# SDCARD.net
KiCad netlist of a schematic drawn in Altium Designer
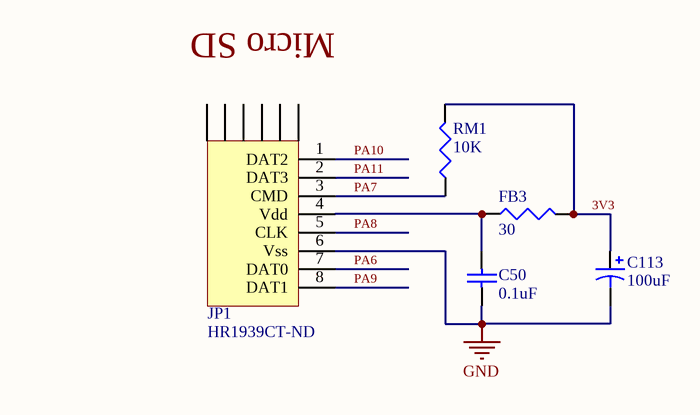
[diagram p0: SDCARD.SchDoc]

(export (version "E")
  (design (tool "Eeschema 10.0.6"))
  (components
    (comp (ref "C50")
      (value "0.1uF")
      (footprint "CAPC2008X06N")
      (description "CAP CER 0.1UF 50V 10% X7R 0805")
      (fields (field (name "Comment") "Kemet_0805_a_0.1uF"))
      (libsource (lib "Capacitors") (part "Kemet_0805_a_0.1uF"))
    )
    (comp (ref "C113")
      (value "100uF")
      (footprint "6032")
      (description "CAP TANT 100UF 10V 10% LOESR SMD")
      (fields (field (name "Comment") "TantCap_6032_100uF"))
      (libsource (lib "my_KEMET") (part "TantCap_6032_100uF"))
    )
    (comp (ref "FB3")
      (value "Murata_a_0805_30_Ohm_100Mhz")
      (footprint "0805")
      (description "FERRITE CHIP 30 OHM 3000MA 0805")
      (fields (field (name "VALUE @ 100MHZ") "30"))
      (libsource (lib "Filters") (part "Murata_a_0805_30_Ohm_100Mhz"))
    )
    (comp (ref "JP1")
      (value "MicroSD Connector")
      (footprint "DM3AT-SF-PEJ")
      (description "CONN MICRO SD R/A PUSH-PUSH SMD")
      (fields (field (name "SUPPLIER PART NUMBER 1") "HR1939CT-ND"))
      (libsource (lib "Hirose Electric CO LTD") (part "MicroSD Connector"))
    )
    (comp (ref "RM1")
      (value "10K")
      (footprint "RES0805")
      (description "RES 10.0K OHM 1/10W .5% 0805 SMD")
      (fields (field (name "Comment") "Susumu_0805_b2_10K"))
      (libsource (lib "Resistors") (part "Susumu_0805_b2_10K"))
    )
  )
  (nets
    (net (code "1") (name "/3V3") (class "Default")
      (node (ref "C113") (pin "1") (pinfunction "1_1") (pintype "passive"))
      (node (ref "FB3") (pin "2") (pinfunction "2_2") (pintype "passive"))
      (node (ref "RM1") (pin "2") (pinfunction "2_2") (pintype "passive"))
    )
    (net (code "2") (name "/PA6") (class "Default")
      (node (ref "JP1") (pin "7") (pinfunction "DAT0_7") (pintype "passive"))
    )
    (net (code "3") (name "/PA7") (class "Default")
      (node (ref "JP1") (pin "3") (pinfunction "CMD_3") (pintype "passive"))
      (node (ref "RM1") (pin "1") (pinfunction "1_1") (pintype "passive"))
    )
    (net (code "4") (name "/PA8") (class "Default")
      (node (ref "JP1") (pin "5") (pinfunction "CLK_5") (pintype "passive"))
    )
    (net (code "5") (name "/PA9") (class "Default")
      (node (ref "JP1") (pin "8") (pinfunction "DAT1_8") (pintype "passive"))
    )
    (net (code "6") (name "/PA10") (class "Default")
      (node (ref "JP1") (pin "1") (pinfunction "DAT2_1") (pintype "passive"))
    )
    (net (code "7") (name "/PA11") (class "Default")
      (node (ref "JP1") (pin "2") (pinfunction "DAT3_2") (pintype "passive"))
    )
    (net (code "8") (name "GND") (class "Default")
      (node (ref "C113") (pin "2") (pinfunction "2_2") (pintype "passive"))
      (node (ref "C50") (pin "1") (pinfunction "1_1") (pintype "passive"))
      (node (ref "JP1") (pin "6") (pinfunction "Vss_6") (pintype "passive"))
    )
    (net (code "9") (name "Net-(JP1-Vdd)") (class "Default")
      (node (ref "C50") (pin "2") (pinfunction "2_2") (pintype "passive"))
      (node (ref "FB3") (pin "1") (pinfunction "1_1") (pintype "passive"))
      (node (ref "JP1") (pin "4") (pinfunction "Vdd_4") (pintype "passive"))
    )
    (net (code "10") (name "unconnected-(JP1-PadC1)") (class "Default")
      (node (ref "JP1") (pin "C1") (pinfunction "C1_C1") (pintype "passive"))
    )
    (net (code "11") (name "unconnected-(JP1-PadC2)") (class "Default")
      (node (ref "JP1") (pin "C2") (pinfunction "C2_C2") (pintype "passive"))
    )
    (net (code "12") (name "unconnected-(JP1-PadC3)") (class "Default")
      (node (ref "JP1") (pin "C3") (pinfunction "C3_C3") (pintype "passive"))
    )
    (net (code "13") (name "unconnected-(JP1-PadC4)") (class "Default")
      (node (ref "JP1") (pin "C4") (pinfunction "C4_C4") (pintype "passive"))
    )
    (net (code "14") (name "unconnected-(JP1-PadC5)") (class "Default")
      (node (ref "JP1") (pin "C5") (pinfunction "C5_C5") (pintype "passive"))
    )
    (net (code "15") (name "unconnected-(JP1-PadC6)") (class "Default")
      (node (ref "JP1") (pin "C6") (pinfunction "C6_C6") (pintype "passive"))
    )
  )
)
